# DK_TT.net
KiCad netlist of a schematic drawn in Altium Designer
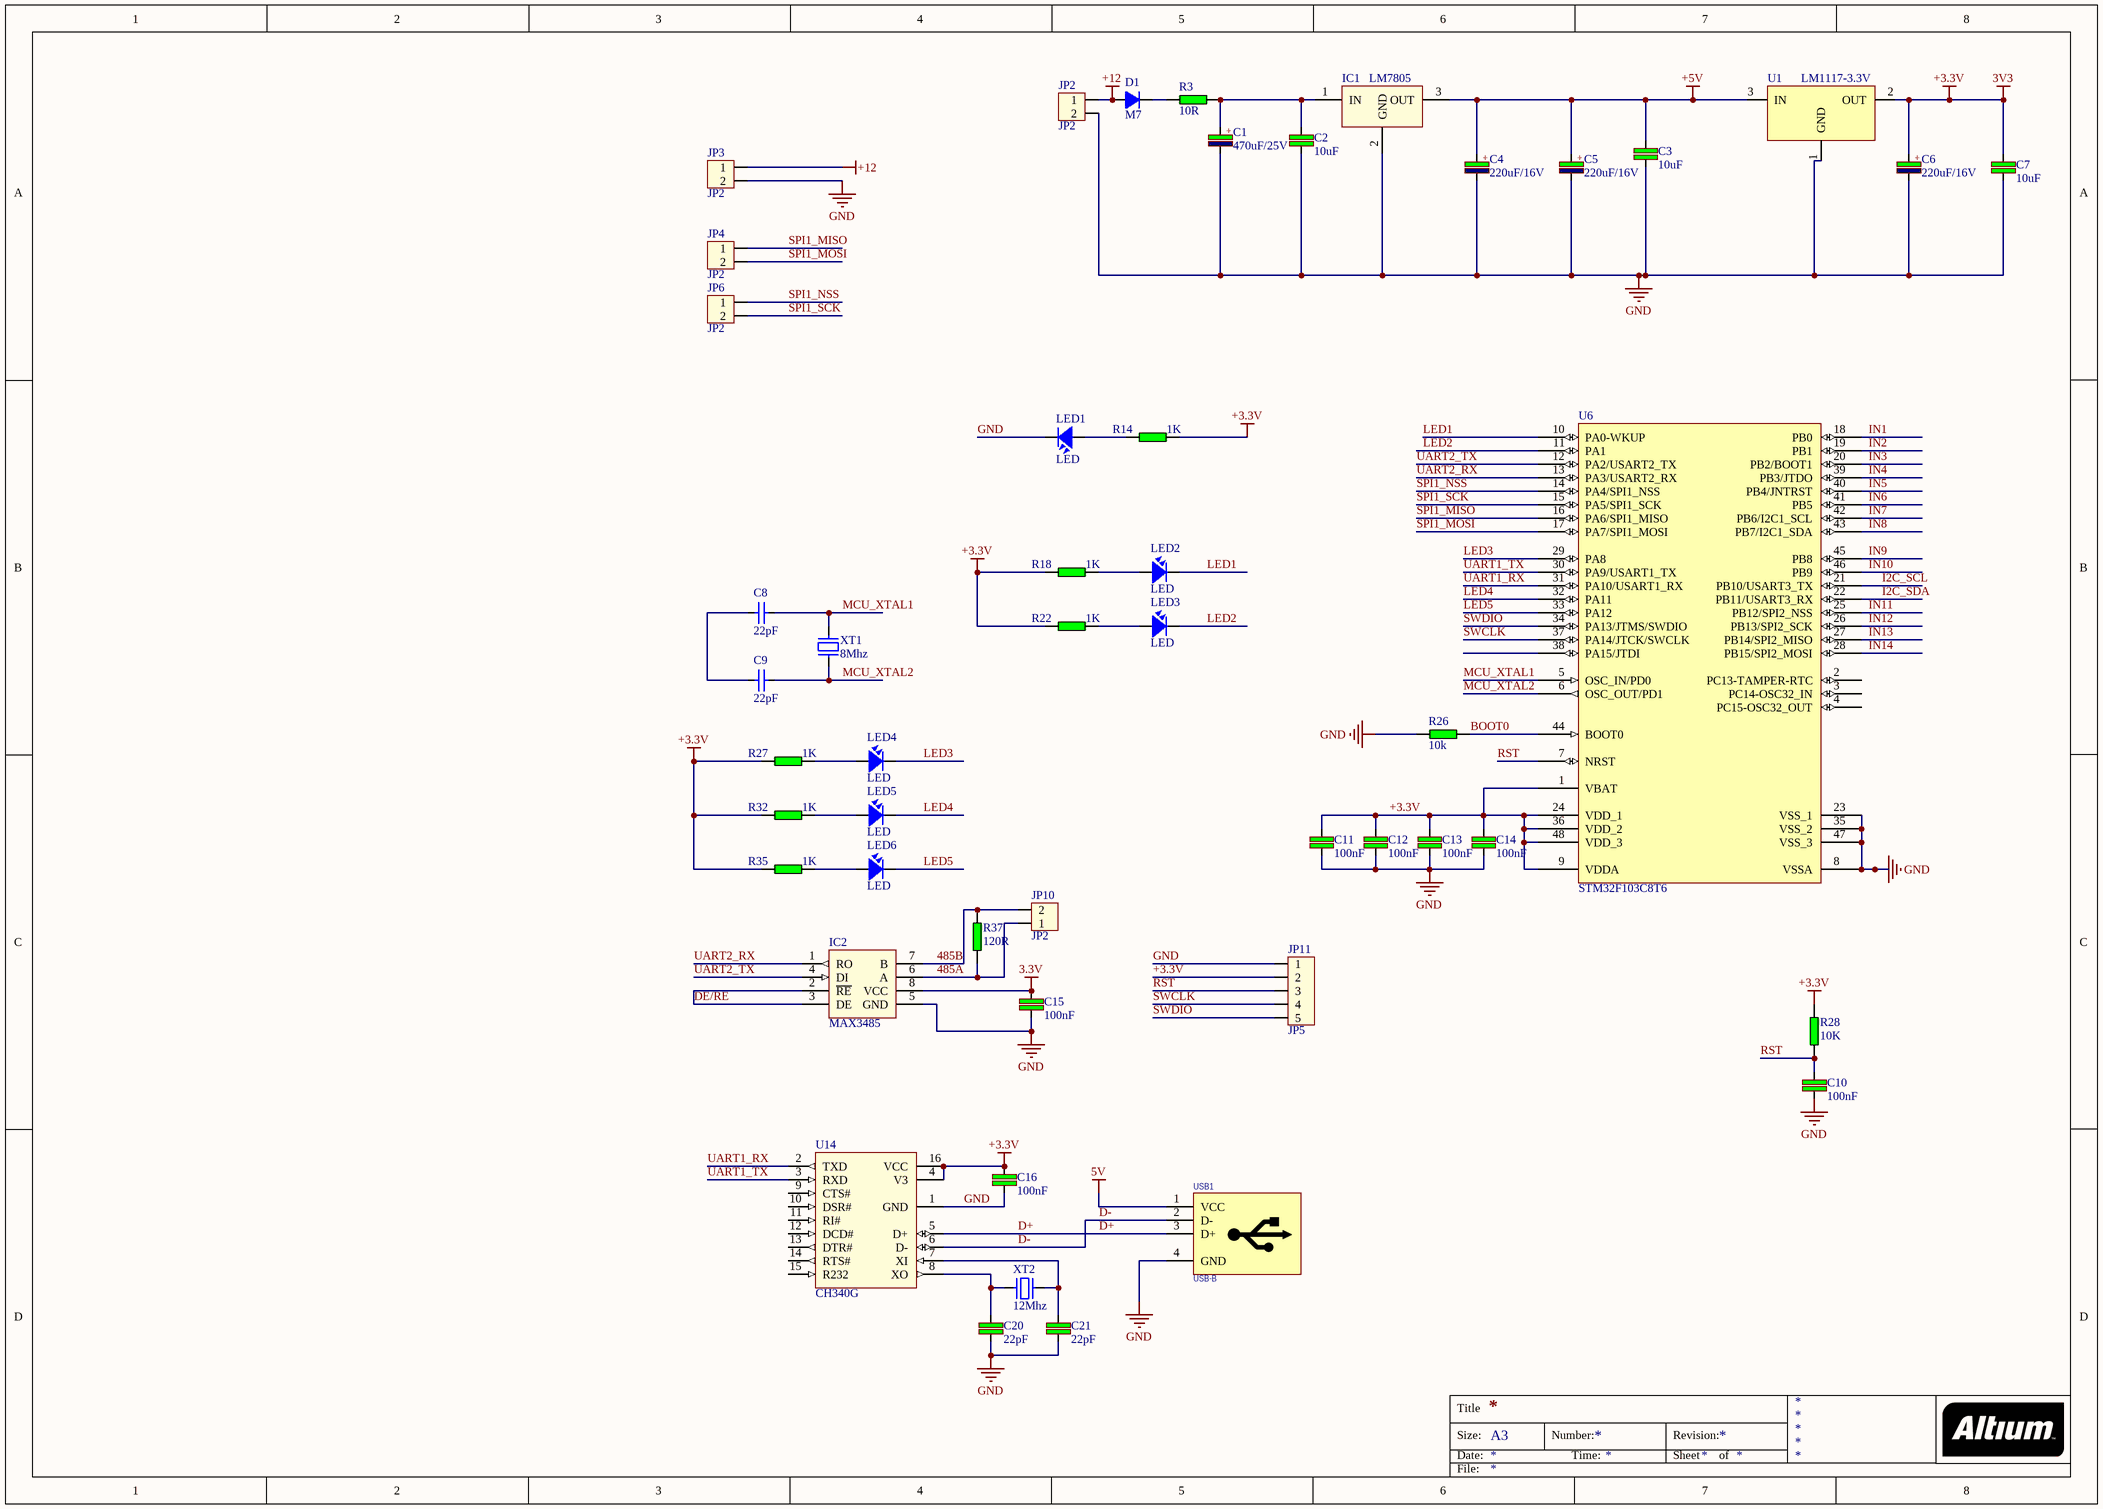
[diagram p0: DK TT.SchDoc]

(export (version "E")
  (design (tool "Eeschema 10.0.6"))
  (components
    (comp (ref "C1")
      (value "470uF/25V")
      (footprint "CP_1000UF/25V_NAM - cao")
      (description "470uF/35V")
      (fields (field (name "MANUFACTURER") "Würth Elektronik") (field (name "PART NUMBER") "860020575014"))
      (libsource (lib "Anh_Trung") (part "CP4"))
    )
    (comp (ref "C2")
      (value "10uF")
      (footprint "C-0805")
      (description "Cap SMD")
      (libsource (lib "") (part "C_1"))
    )
    (comp (ref "C3")
      (value "10uF")
      (footprint "C-0805")
      (description "Cap SMD")
      (libsource (lib "") (part "C_1"))
    )
    (comp (ref "C4")
      (value "220uF/16V")
      (footprint "CA-ALU-5L")
      (description "Cap 100uF/35V - 470uF/16V")
      (libsource (lib "Anh_Trung") (part "CP3"))
    )
    (comp (ref "C5")
      (value "220uF/16V")
      (footprint "CA-ALU-5L")
      (description "Cap 100uF/35V - 470uF/16V")
      (libsource (lib "Anh_Trung") (part "CP3"))
    )
    (comp (ref "C6")
      (value "220uF/16V")
      (footprint "CA-ALU-5L")
      (description "Cap 100uF/35V - 470uF/16V")
      (libsource (lib "Anh_Trung") (part "CP3"))
    )
    (comp (ref "C7")
      (value "10uF")
      (footprint "C-0805")
      (description "Cap SMD")
      (libsource (lib "") (part "C_1"))
    )
    (comp (ref "C8")
      (value "22pF")
      (footprint "CAP_0402")
      (description "Capacitor")
      (fields (field (name "PUBLISHER") "Altium Limited"))
      (libsource (lib "My Library") (part "CapSMD"))
    )
    (comp (ref "C9")
      (value "22pF")
      (footprint "CAP_0402")
      (description "Capacitor")
      (fields (field (name "PUBLISHER") "Altium Limited"))
      (libsource (lib "My Library") (part "CapSMD"))
    )
    (comp (ref "C10")
      (value "100nF")
      (footprint "C-0805")
      (description "Cap SMD")
      (libsource (lib "altium-import") (part "root_1_C_"))
    )
    (comp (ref "C11")
      (value "100nF")
      (footprint "C-0805")
      (description "Cap SMD")
      (libsource (lib "heromap") (part "C"))
    )
    (comp (ref "C12")
      (value "100nF")
      (footprint "C-0805")
      (description "Cap SMD")
      (libsource (lib "heromap") (part "C"))
    )
    (comp (ref "C13")
      (value "100nF")
      (footprint "C-0805")
      (description "Cap SMD")
      (libsource (lib "heromap") (part "C"))
    )
    (comp (ref "C14")
      (value "100nF")
      (footprint "C-0805")
      (description "Cap SMD")
      (libsource (lib "heromap") (part "C"))
    )
    (comp (ref "C15")
      (value "100nF")
      (footprint "C-0805")
      (description "Cap SMD")
      (fields
        (field (name "MANUFACTURER") "Samsung Electro-Mechanics")
        (field (name "PART NUMBER") "CL21B104KBCNNWC")
      )
      (libsource (lib "") (part "C_1"))
    )
    (comp (ref "C16")
      (value "100nF")
      (footprint "C-0805")
      (description "Cap SMD")
      (fields
        (field (name "MANUFACTURER") "Samsung Electro-Mechanics")
        (field (name "PART NUMBER") "CL21B104KBCNNWC")
      )
      (libsource (lib "Anh_Trung") (part "C"))
    )
    (comp (ref "C20")
      (value "22pF")
      (footprint "C-0805")
      (description "Cap SMD")
      (fields
        (field (name "MANUFACTURER") "Samsung Electro-Mechanics")
        (field (name "PART NUMBER") "CL21C220JBANFNC")
      )
      (libsource (lib "Anh_Trung") (part "C"))
    )
    (comp (ref "C21")
      (value "22pF")
      (footprint "C-0805")
      (description "Cap SMD")
      (fields
        (field (name "MANUFACTURER") "Samsung Electro-Mechanics")
        (field (name "PART NUMBER") "CL21C220JBANFNC")
      )
      (libsource (lib "Anh_Trung") (part "C"))
    )
    (comp (ref "D1")
      (value "M7")
      (footprint "SMA11")
      (description "Diode 1A")
      (libsource (lib "Anh_Trung") (part "D1A"))
    )
    (comp (ref "IC1")
      (value "LM7805")
      (footprint "Anh_Trung:TO-252 7805")
      (description "On ap +, from + 5 to + 24VDC")
      (libsource (lib "Anh_Trung") (part "LM78xx"))
    )
    (comp (ref "IC2")
      (value "MAX3485")
      (footprint "SOIC-8")
      (description "IC TRANSCEIVER HALF 1/1 SOT23-8")
      (fields (field (name "MANUFACTURER") "Maxim Integrated") (field (name "PART NUMBER") "MAX3362EKA+T"))
      (libsource (lib "Anh_Trung") (part "MAX3362EKA+T"))
    )
    (comp (ref "JP2")
      (value "JP2")
      (footprint "KF2-5.08T")
      (description "Connector 2")
      (libsource (lib "Anh_Trung") (part "Con2"))
    )
    (comp (ref "JP3")
      (value "JP2")
      (footprint "KF2-5.08T")
      (description "Connector 2")
      (libsource (lib "Anh_Trung") (part "Con2"))
    )
    (comp (ref "JP4")
      (value "JP2")
      (footprint "KF2-5.08T")
      (description "Connector 2")
      (libsource (lib "Anh_Trung") (part "Con2"))
    )
    (comp (ref "JP6")
      (value "JP2")
      (footprint "KF2-5.08T")
      (description "Connector 2")
      (libsource (lib "Anh_Trung") (part "Con2"))
    )
    (comp (ref "JP10")
      (value "JP2")
      (footprint "KF2-5.08T")
      (description "Connector 2")
      (libsource (lib "") (part "Con2_1"))
    )
    (comp (ref "JP11")
      (value "JP5")
      (footprint "JP5-D1T")
      (description "Connector 5")
      (libsource (lib "Anh_Trung") (part "Con5"))
    )
    (comp (ref "LED1")
      (value "LED")
      (footprint "LED-0805-Red")
      (description "LED Single colour Green and Red")
      (libsource (lib "My Library") (part "LED"))
    )
    (comp (ref "LED2")
      (value "LED")
      (footprint "LED-0805-Red")
      (description "LED Single colour Green and Red")
      (libsource (lib "My Library") (part "LED"))
    )
    (comp (ref "LED3")
      (value "LED")
      (footprint "LED-0805-Red")
      (description "LED Single colour Green and Red")
      (libsource (lib "My Library") (part "LED"))
    )
    (comp (ref "LED4")
      (value "LED")
      (footprint "LED-3")
      (description "LED Single colour Green and Red")
      (libsource (lib "VioletofSun") (part "LED"))
    )
    (comp (ref "LED5")
      (value "LED")
      (footprint "LED-3")
      (description "LED Single colour Green and Red")
      (libsource (lib "VioletofSun") (part "LED"))
    )
    (comp (ref "LED6")
      (value "LED")
      (footprint "LED-3")
      (description "LED Single colour Green and Red")
      (libsource (lib "VioletofSun") (part "LED"))
    )
    (comp (ref "R3")
      (value "10R")
      (footprint "R-1206")
      (description "Resistor 1/4W")
      (libsource (lib "") (part "RES_1"))
    )
    (comp (ref "R14")
      (value "1K")
      (footprint "R-0805")
      (description "Resistor 1/4W")
      (libsource (lib "heromap") (part "RES"))
    )
    (comp (ref "R18")
      (value "1K")
      (footprint "R-0805")
      (description "Resistor 1/4W")
      (libsource (lib "heromap") (part "RES"))
    )
    (comp (ref "R22")
      (value "1K")
      (footprint "R-0805")
      (description "Resistor 1/4W")
      (libsource (lib "heromap") (part "RES"))
    )
    (comp (ref "R26")
      (value "10k")
      (footprint "R-0805")
      (description "Resistor 1/4W")
      (libsource (lib "") (part "RES_2"))
    )
    (comp (ref "R27")
      (value "1K")
      (footprint "R-0805")
      (description "Resistor 1/4W")
      (libsource (lib "heromap") (part "RES"))
    )
    (comp (ref "R28")
      (value "10K")
      (footprint "R-0805")
      (description "Resistor 1/4W")
      (libsource (lib "altium-import") (part "root_3_RES_1_"))
    )
    (comp (ref "R32")
      (value "1K")
      (footprint "R-0805")
      (description "Resistor 1/4W")
      (libsource (lib "heromap") (part "RES"))
    )
    (comp (ref "R35")
      (value "1K")
      (footprint "R-0805")
      (description "Resistor 1/4W")
      (libsource (lib "heromap") (part "RES"))
    )
    (comp (ref "R37")
      (value "120R")
      (footprint "R-0805")
      (description "Resistor 1/4W")
      (libsource (lib "") (part "RES_3"))
    )
    (comp (ref "U1")
      (value "LM1117-3.3V")
      (footprint "SOT223-4N")
      (fields (field (name "CREATOR") "Nguyen Ba Bien"))
      (libsource (lib "Anh_Trung") (part "LM1117"))
    )
    (comp (ref "U6")
      (value "STM32F103C8T6")
      (footprint "LQFP48_L")
      (libsource (lib "heromap") (part "STM32F103C8T6"))
    )
    (comp (ref "U14")
      (value "CH340G")
      (footprint "SOIC-16")
      (description "USB to UART Interface")
      (fields (field (name "MANUFACTURER") "WCH"))
      (libsource (lib "Anh_Trung") (part "CH340G"))
    )
    (comp (ref "USB1")
      (value "USB-B")
      (footprint "USB-B")
      (description "CONN USB 2.0 RT ANGLE TYPE B")
      (fields (field (name "MANUFACTURER") "Stewart Connector") (field (name "PART NUMBER") "SS-52300-001"))
      (libsource (lib "Anh_Trung") (part "USB-B"))
    )
    (comp (ref "XT1")
      (value "8Mhz")
      (footprint "XTAL-RU49/4")
      (description "CRYSTAL 12.0000MHZ 18PF SMD")
      (fields
        (field (name "MANUFACTURER") "IQD Frequency Products")
        (field (name "PART NUMBER") "LFXTAL036356REEL")
      )
      (libsource (lib "Anh_Trung") (part "XT2"))
    )
    (comp (ref "XT2")
      (value "12Mhz")
      (footprint "XTAL-RU49/4")
      (description "CRYSTAL 12.0000MHZ 18PF SMD")
      (fields
        (field (name "MANUFACTURER") "IQD Frequency Products")
        (field (name "PART NUMBER") "LFXTAL036356REEL")
      )
      (libsource (lib "Anh_Trung") (part "XT2"))
    )
  )
  (nets
    (net (code "1") (name "+3.3V") (class "Default")
      (node (ref "C11") (pin "1") (pinfunction "1_1") (pintype "passive"))
      (node (ref "C12") (pin "1") (pinfunction "1_1") (pintype "passive"))
      (node (ref "C13") (pin "1") (pinfunction "1_1") (pintype "passive"))
      (node (ref "C14") (pin "1") (pinfunction "1_1") (pintype "passive"))
      (node (ref "C16") (pin "2") (pinfunction "2_2") (pintype "passive"))
      (node (ref "C6") (pin "1") (pinfunction "1_1") (pintype "passive"))
      (node (ref "C7") (pin "2") (pinfunction "2_2") (pintype "passive"))
      (node (ref "JP11") (pin "2") (pinfunction "2_2") (pintype "passive"))
      (node (ref "R14") (pin "1") (pinfunction "1_1") (pintype "passive"))
      (node (ref "R18") (pin "2") (pinfunction "2_2") (pintype "passive"))
      (node (ref "R22") (pin "2") (pinfunction "2_2") (pintype "passive"))
      (node (ref "R27") (pin "2") (pinfunction "2_2") (pintype "passive"))
      (node (ref "R28") (pin "1") (pinfunction "1_1") (pintype "passive"))
      (node (ref "R32") (pin "2") (pinfunction "2_2") (pintype "passive"))
      (node (ref "R35") (pin "2") (pinfunction "2_2") (pintype "passive"))
      (node (ref "U1") (pin "2") (pinfunction "OUT_2") (pintype "passive"))
      (node (ref "U14") (pin "16") (pinfunction "VCC_16") (pintype "power_in"))
      (node (ref "U14") (pin "4") (pinfunction "V3_4") (pintype "passive"))
      (node (ref "U6") (pin "1") (pinfunction "VBAT_1") (pintype "power_in"))
      (node (ref "U6") (pin "24") (pinfunction "VDD_1_24") (pintype "power_in"))
      (node (ref "U6") (pin "36") (pinfunction "VDD_2_36") (pintype "power_in"))
      (node (ref "U6") (pin "48") (pinfunction "VDD_3_48") (pintype "power_in"))
      (node (ref "U6") (pin "9") (pinfunction "VDDA_9") (pintype "power_in"))
    )
    (net (code "2") (name "+5V") (class "Default")
      (node (ref "C3") (pin "2") (pinfunction "2_2") (pintype "passive"))
      (node (ref "C4") (pin "1") (pinfunction "1_1") (pintype "passive"))
      (node (ref "C5") (pin "1") (pinfunction "1_1") (pintype "passive"))
      (node (ref "IC1") (pin "3") (pinfunction "OUT_3") (pintype "passive"))
      (node (ref "U1") (pin "3") (pinfunction "IN_3") (pintype "passive"))
    )
    (net (code "3") (name "+12") (class "Default")
      (node (ref "D1") (pin "1") (pinfunction "A_1") (pintype "passive"))
      (node (ref "JP2") (pin "1") (pinfunction "1_1") (pintype "passive"))
      (node (ref "JP3") (pin "1") (pinfunction "1_1") (pintype "passive"))
    )
    (net (code "4") (name "/485A") (class "Default")
      (node (ref "IC2") (pin "6") (pinfunction "A_6") (pintype "passive"))
      (node (ref "JP10") (pin "1") (pinfunction "1_1") (pintype "passive"))
      (node (ref "R37") (pin "2") (pinfunction "2_2") (pintype "passive"))
    )
    (net (code "5") (name "/485B") (class "Default")
      (node (ref "IC2") (pin "7") (pinfunction "B_7") (pintype "passive"))
      (node (ref "JP10") (pin "2") (pinfunction "2_2") (pintype "passive"))
      (node (ref "R37") (pin "1") (pinfunction "1_1") (pintype "passive"))
    )
    (net (code "6") (name "/BOOT0") (class "Default")
      (node (ref "R26") (pin "2") (pinfunction "2_2") (pintype "passive"))
      (node (ref "U6") (pin "44") (pinfunction "BOOT0_44") (pintype "input"))
    )
    (net (code "7") (name "/D+") (class "Default")
      (node (ref "U14") (pin "5") (pinfunction "D+_5") (pintype "bidirectional"))
      (node (ref "USB1") (pin "3") (pinfunction "D+_3") (pintype "passive"))
    )
    (net (code "8") (name "/D-") (class "Default")
      (node (ref "U14") (pin "6") (pinfunction "D-_6") (pintype "bidirectional"))
      (node (ref "USB1") (pin "2") (pinfunction "D-_2") (pintype "passive"))
    )
    (net (code "9") (name "/DE{slash}RE") (class "Default")
      (node (ref "IC2") (pin "2") (pinfunction "~{RE}_2") (pintype "passive"))
      (node (ref "IC2") (pin "3") (pinfunction "DE_3") (pintype "passive"))
    )
    (net (code "10") (name "/I2C_SCL") (class "Default")
      (node (ref "U6") (pin "21") (pinfunction "PB10/USART3_TX_21") (pintype "bidirectional"))
    )
    (net (code "11") (name "/I2C_SDA") (class "Default")
      (node (ref "U6") (pin "22") (pinfunction "PB11/USART3_RX_22") (pintype "bidirectional"))
    )
    (net (code "12") (name "/IN1") (class "Default")
      (node (ref "U6") (pin "18") (pinfunction "PB0_18") (pintype "bidirectional"))
    )
    (net (code "13") (name "/IN2") (class "Default")
      (node (ref "U6") (pin "19") (pinfunction "PB1_19") (pintype "bidirectional"))
    )
    (net (code "14") (name "/IN3") (class "Default")
      (node (ref "U6") (pin "20") (pinfunction "PB2/BOOT1_20") (pintype "bidirectional"))
    )
    (net (code "15") (name "/IN4") (class "Default")
      (node (ref "U6") (pin "39") (pinfunction "PB3/JTDO_39") (pintype "bidirectional"))
    )
    (net (code "16") (name "/IN5") (class "Default")
      (node (ref "U6") (pin "40") (pinfunction "PB4/JNTRST_40") (pintype "bidirectional"))
    )
    (net (code "17") (name "/IN6") (class "Default")
      (node (ref "U6") (pin "41") (pinfunction "PB5_41") (pintype "bidirectional"))
    )
    (net (code "18") (name "/IN7") (class "Default")
      (node (ref "U6") (pin "42") (pinfunction "PB6/I2C1_SCL_42") (pintype "bidirectional"))
    )
    (net (code "19") (name "/IN8") (class "Default")
      (node (ref "U6") (pin "43") (pinfunction "PB7/I2C1_SDA_43") (pintype "bidirectional"))
    )
    (net (code "20") (name "/IN9") (class "Default")
      (node (ref "U6") (pin "45") (pinfunction "PB8_45") (pintype "bidirectional"))
    )
    (net (code "21") (name "/IN10") (class "Default")
      (node (ref "U6") (pin "46") (pinfunction "PB9_46") (pintype "bidirectional"))
    )
    (net (code "22") (name "/IN11") (class "Default")
      (node (ref "U6") (pin "25") (pinfunction "PB12/SPI2_NSS_25") (pintype "bidirectional"))
    )
    (net (code "23") (name "/IN12") (class "Default")
      (node (ref "U6") (pin "26") (pinfunction "PB13/SPI2_SCK_26") (pintype "bidirectional"))
    )
    (net (code "24") (name "/IN13") (class "Default")
      (node (ref "U6") (pin "27") (pinfunction "PB14/SPI2_MISO_27") (pintype "bidirectional"))
    )
    (net (code "25") (name "/IN14") (class "Default")
      (node (ref "U6") (pin "28") (pinfunction "PB15/SPI2_MOSI_28") (pintype "bidirectional"))
    )
    (net (code "26") (name "/LED1") (class "Default")
      (node (ref "LED2") (pin "2") (pinfunction "2_2") (pintype "passive"))
      (node (ref "U6") (pin "10") (pinfunction "PA0-WKUP_10") (pintype "bidirectional"))
    )
    (net (code "27") (name "/LED2") (class "Default")
      (node (ref "LED3") (pin "2") (pinfunction "2_2") (pintype "passive"))
      (node (ref "U6") (pin "11") (pinfunction "PA1_11") (pintype "bidirectional"))
    )
    (net (code "28") (name "/LED3") (class "Default")
      (node (ref "LED4") (pin "2") (pinfunction "2_2") (pintype "passive"))
      (node (ref "U6") (pin "29") (pinfunction "PA8_29") (pintype "bidirectional"))
    )
    (net (code "29") (name "/LED4") (class "Default")
      (node (ref "LED5") (pin "2") (pinfunction "2_2") (pintype "passive"))
      (node (ref "U6") (pin "32") (pinfunction "PA11_32") (pintype "bidirectional"))
    )
    (net (code "30") (name "/LED5") (class "Default")
      (node (ref "LED6") (pin "2") (pinfunction "2_2") (pintype "passive"))
      (node (ref "U6") (pin "33") (pinfunction "PA12_33") (pintype "bidirectional"))
    )
    (net (code "31") (name "/MCU_XTAL1") (class "Default")
      (node (ref "C8") (pin "1") (pinfunction "1_1") (pintype "passive"))
      (node (ref "U6") (pin "5") (pinfunction "OSC_IN/PD0_5") (pintype "input"))
      (node (ref "XT1") (pin "1") (pinfunction "1_1") (pintype "passive"))
    )
    (net (code "32") (name "/MCU_XTAL2") (class "Default")
      (node (ref "C9") (pin "1") (pinfunction "1_1") (pintype "passive"))
      (node (ref "U6") (pin "6") (pinfunction "OSC_OUT/PD1_6") (pintype "output"))
      (node (ref "XT1") (pin "2") (pinfunction "2_2") (pintype "passive"))
    )
    (net (code "33") (name "/RST") (class "Default")
      (node (ref "C10") (pin "2") (pinfunction "2_2") (pintype "passive"))
      (node (ref "JP11") (pin "3") (pinfunction "3_3") (pintype "passive"))
      (node (ref "R28") (pin "2") (pinfunction "2_2") (pintype "passive"))
      (node (ref "U6") (pin "7") (pinfunction "NRST_7") (pintype "bidirectional"))
    )
    (net (code "34") (name "/SPI1_MISO") (class "Default")
      (node (ref "JP4") (pin "1") (pinfunction "1_1") (pintype "passive"))
      (node (ref "U6") (pin "16") (pinfunction "PA6/SPI1_MISO_16") (pintype "bidirectional"))
    )
    (net (code "35") (name "/SPI1_MOSI") (class "Default")
      (node (ref "JP4") (pin "2") (pinfunction "2_2") (pintype "passive"))
      (node (ref "U6") (pin "17") (pinfunction "PA7/SPI1_MOSI_17") (pintype "bidirectional"))
    )
    (net (code "36") (name "/SPI1_NSS") (class "Default")
      (node (ref "JP6") (pin "1") (pinfunction "1_1") (pintype "passive"))
      (node (ref "U6") (pin "14") (pinfunction "PA4/SPI1_NSS_14") (pintype "bidirectional"))
    )
    (net (code "37") (name "/SPI1_SCK") (class "Default")
      (node (ref "JP6") (pin "2") (pinfunction "2_2") (pintype "passive"))
      (node (ref "U6") (pin "15") (pinfunction "PA5/SPI1_SCK_15") (pintype "bidirectional"))
    )
    (net (code "38") (name "/SWCLK") (class "Default")
      (node (ref "JP11") (pin "4") (pinfunction "4_4") (pintype "passive"))
      (node (ref "U6") (pin "37") (pinfunction "PA14/JTCK/SWCLK_37") (pintype "bidirectional"))
    )
    (net (code "39") (name "/SWDIO") (class "Default")
      (node (ref "JP11") (pin "5") (pinfunction "5_5") (pintype "passive"))
      (node (ref "U6") (pin "34") (pinfunction "PA13/JTMS/SWDIO_34") (pintype "bidirectional"))
    )
    (net (code "40") (name "/UART1_RX") (class "Default")
      (node (ref "U14") (pin "2") (pinfunction "TXD_2") (pintype "output"))
      (node (ref "U6") (pin "31") (pinfunction "PA10/USART1_RX_31") (pintype "bidirectional"))
    )
    (net (code "41") (name "/UART1_TX") (class "Default")
      (node (ref "U14") (pin "3") (pinfunction "RXD_3") (pintype "input"))
      (node (ref "U6") (pin "30") (pinfunction "PA9/USART1_TX_30") (pintype "bidirectional"))
    )
    (net (code "42") (name "/UART2_RX") (class "Default")
      (node (ref "IC2") (pin "1") (pinfunction "RO_1") (pintype "output"))
      (node (ref "U6") (pin "13") (pinfunction "PA3/USART2_RX_13") (pintype "bidirectional"))
    )
    (net (code "43") (name "/UART2_TX") (class "Default")
      (node (ref "IC2") (pin "4") (pinfunction "DI_4") (pintype "input"))
      (node (ref "U6") (pin "12") (pinfunction "PA2/USART2_TX_12") (pintype "bidirectional"))
    )
    (net (code "44") (name "3.3V") (class "Default")
      (node (ref "C15") (pin "1") (pinfunction "1_1") (pintype "passive"))
      (node (ref "IC2") (pin "8") (pinfunction "VCC_8") (pintype "passive"))
    )
    (net (code "45") (name "5V") (class "Default")
      (node (ref "USB1") (pin "1") (pinfunction "VCC_1") (pintype "passive"))
    )
    (net (code "46") (name "GND") (class "Default")
      (node (ref "C1") (pin "2") (pinfunction "2_2") (pintype "passive"))
      (node (ref "C10") (pin "1") (pinfunction "1_1") (pintype "passive"))
      (node (ref "C11") (pin "2") (pinfunction "2_2") (pintype "passive"))
      (node (ref "C12") (pin "2") (pinfunction "2_2") (pintype "passive"))
      (node (ref "C13") (pin "2") (pinfunction "2_2") (pintype "passive"))
      (node (ref "C14") (pin "2") (pinfunction "2_2") (pintype "passive"))
      (node (ref "C15") (pin "2") (pinfunction "2_2") (pintype "passive"))
      (node (ref "C16") (pin "1") (pinfunction "1_1") (pintype "passive"))
      (node (ref "C2") (pin "1") (pinfunction "1_1") (pintype "passive"))
      (node (ref "C20") (pin "1") (pinfunction "1_1") (pintype "passive"))
      (node (ref "C21") (pin "1") (pinfunction "1_1") (pintype "passive"))
      (node (ref "C3") (pin "1") (pinfunction "1_1") (pintype "passive"))
      (node (ref "C4") (pin "2") (pinfunction "2_2") (pintype "passive"))
      (node (ref "C5") (pin "2") (pinfunction "2_2") (pintype "passive"))
      (node (ref "C6") (pin "2") (pinfunction "2_2") (pintype "passive"))
      (node (ref "C7") (pin "1") (pinfunction "1_1") (pintype "passive"))
      (node (ref "IC1") (pin "2") (pinfunction "GND_2") (pintype "passive"))
      (node (ref "IC2") (pin "5") (pinfunction "GND_5") (pintype "passive"))
      (node (ref "JP11") (pin "1") (pinfunction "1_1") (pintype "passive"))
      (node (ref "JP2") (pin "2") (pinfunction "2_2") (pintype "passive"))
      (node (ref "JP3") (pin "2") (pinfunction "2_2") (pintype "passive"))
      (node (ref "LED1") (pin "2") (pinfunction "2_2") (pintype "passive"))
      (node (ref "R26") (pin "1") (pinfunction "1_1") (pintype "passive"))
      (node (ref "U1") (pin "1") (pinfunction "GND_1") (pintype "passive"))
      (node (ref "U14") (pin "1") (pinfunction "GND_1") (pintype "passive"))
      (node (ref "U6") (pin "23") (pinfunction "VSS_1_23") (pintype "power_in"))
      (node (ref "U6") (pin "35") (pinfunction "VSS_2_35") (pintype "power_in"))
      (node (ref "U6") (pin "47") (pinfunction "VSS_3_47") (pintype "power_in"))
      (node (ref "U6") (pin "8") (pinfunction "VSSA_8") (pintype "power_in"))
      (node (ref "USB1") (pin "4") (pinfunction "GND_4") (pintype "passive"))
    )
    (net (code "47") (name "Net-(C8-Pad2)") (class "Default")
      (node (ref "C8") (pin "2") (pinfunction "2_2") (pintype "passive"))
      (node (ref "C9") (pin "2") (pinfunction "2_2") (pintype "passive"))
    )
    (net (code "48") (name "Net-(D1-K)") (class "Default")
      (node (ref "D1") (pin "2") (pinfunction "K_2") (pintype "passive"))
      (node (ref "R3") (pin "1") (pinfunction "1_1") (pintype "passive"))
    )
    (net (code "49") (name "Net-(IC1-IN)") (class "Default")
      (node (ref "C1") (pin "1") (pinfunction "1_1") (pintype "passive"))
      (node (ref "C2") (pin "2") (pinfunction "2_2") (pintype "passive"))
      (node (ref "IC1") (pin "1") (pinfunction "IN_1") (pintype "passive"))
      (node (ref "R3") (pin "2") (pinfunction "2_2") (pintype "passive"))
    )
    (net (code "50") (name "Net-(LED1-Pad1)") (class "Default")
      (node (ref "LED1") (pin "1") (pinfunction "1_1") (pintype "passive"))
      (node (ref "R14") (pin "2") (pinfunction "2_2") (pintype "passive"))
    )
    (net (code "51") (name "Net-(LED2-Pad1)") (class "Default")
      (node (ref "LED2") (pin "1") (pinfunction "1_1") (pintype "passive"))
      (node (ref "R18") (pin "1") (pinfunction "1_1") (pintype "passive"))
    )
    (net (code "52") (name "Net-(LED3-Pad1)") (class "Default")
      (node (ref "LED3") (pin "1") (pinfunction "1_1") (pintype "passive"))
      (node (ref "R22") (pin "1") (pinfunction "1_1") (pintype "passive"))
    )
    (net (code "53") (name "Net-(LED4-Pad1)") (class "Default")
      (node (ref "LED4") (pin "1") (pinfunction "1_1") (pintype "passive"))
      (node (ref "R27") (pin "1") (pinfunction "1_1") (pintype "passive"))
    )
    (net (code "54") (name "Net-(LED5-Pad1)") (class "Default")
      (node (ref "LED5") (pin "1") (pinfunction "1_1") (pintype "passive"))
      (node (ref "R32") (pin "1") (pinfunction "1_1") (pintype "passive"))
    )
    (net (code "55") (name "Net-(LED6-Pad1)") (class "Default")
      (node (ref "LED6") (pin "1") (pinfunction "1_1") (pintype "passive"))
      (node (ref "R35") (pin "1") (pinfunction "1_1") (pintype "passive"))
    )
    (net (code "56") (name "Net-(U14-XI)") (class "Default")
      (node (ref "C21") (pin "2") (pinfunction "2_2") (pintype "passive"))
      (node (ref "U14") (pin "7") (pinfunction "XI_7") (pintype "input"))
      (node (ref "XT2") (pin "2") (pinfunction "2_2") (pintype "passive"))
    )
    (net (code "57") (name "Net-(U14-XO)") (class "Default")
      (node (ref "C20") (pin "2") (pinfunction "2_2") (pintype "passive"))
      (node (ref "U14") (pin "8") (pinfunction "XO_8") (pintype "output"))
      (node (ref "XT2") (pin "1") (pinfunction "1_1") (pintype "passive"))
    )
    (net (code "58") (name "unconnected-(U6-PA15{slash}JTDI-Pad38)") (class "Default")
      (node (ref "U6") (pin "38") (pinfunction "PA15/JTDI_38") (pintype "bidirectional"))
    )
    (net (code "59") (name "unconnected-(U6-PC13-TAMPER-RTC-Pad2)") (class "Default")
      (node (ref "U6") (pin "2") (pinfunction "PC13-TAMPER-RTC_2") (pintype "bidirectional"))
    )
    (net (code "60") (name "unconnected-(U6-PC14-OSC32_IN-Pad3)") (class "Default")
      (node (ref "U6") (pin "3") (pinfunction "PC14-OSC32_IN_3") (pintype "bidirectional"))
    )
    (net (code "61") (name "unconnected-(U6-PC15-OSC32_OUT-Pad4)") (class "Default")
      (node (ref "U6") (pin "4") (pinfunction "PC15-OSC32_OUT_4") (pintype "bidirectional"))
    )
    (net (code "62") (name "unconnected-(U14-CTS#-Pad9)") (class "Default")
      (node (ref "U14") (pin "9") (pinfunction "CTS#_9") (pintype "input"))
    )
    (net (code "63") (name "unconnected-(U14-DCD#-Pad12)") (class "Default")
      (node (ref "U14") (pin "12") (pinfunction "DCD#_12") (pintype "input"))
    )
    (net (code "64") (name "unconnected-(U14-DSR#-Pad10)") (class "Default")
      (node (ref "U14") (pin "10") (pinfunction "DSR#_10") (pintype "input"))
    )
    (net (code "65") (name "unconnected-(U14-DTR#-Pad13)") (class "Default")
      (node (ref "U14") (pin "13") (pinfunction "DTR#_13") (pintype "output"))
    )
    (net (code "66") (name "unconnected-(U14-R232-Pad15)") (class "Default")
      (node (ref "U14") (pin "15") (pinfunction "R232_15") (pintype "input"))
    )
    (net (code "67") (name "unconnected-(U14-RI#-Pad11)") (class "Default")
      (node (ref "U14") (pin "11") (pinfunction "RI#_11") (pintype "input"))
    )
    (net (code "68") (name "unconnected-(U14-RTS#-Pad14)") (class "Default")
      (node (ref "U14") (pin "14") (pinfunction "RTS#_14") (pintype "output"))
    )
  )
)
